# LSF0204RGYR.net
KiCad netlist of a schematic drawn in EAGLE
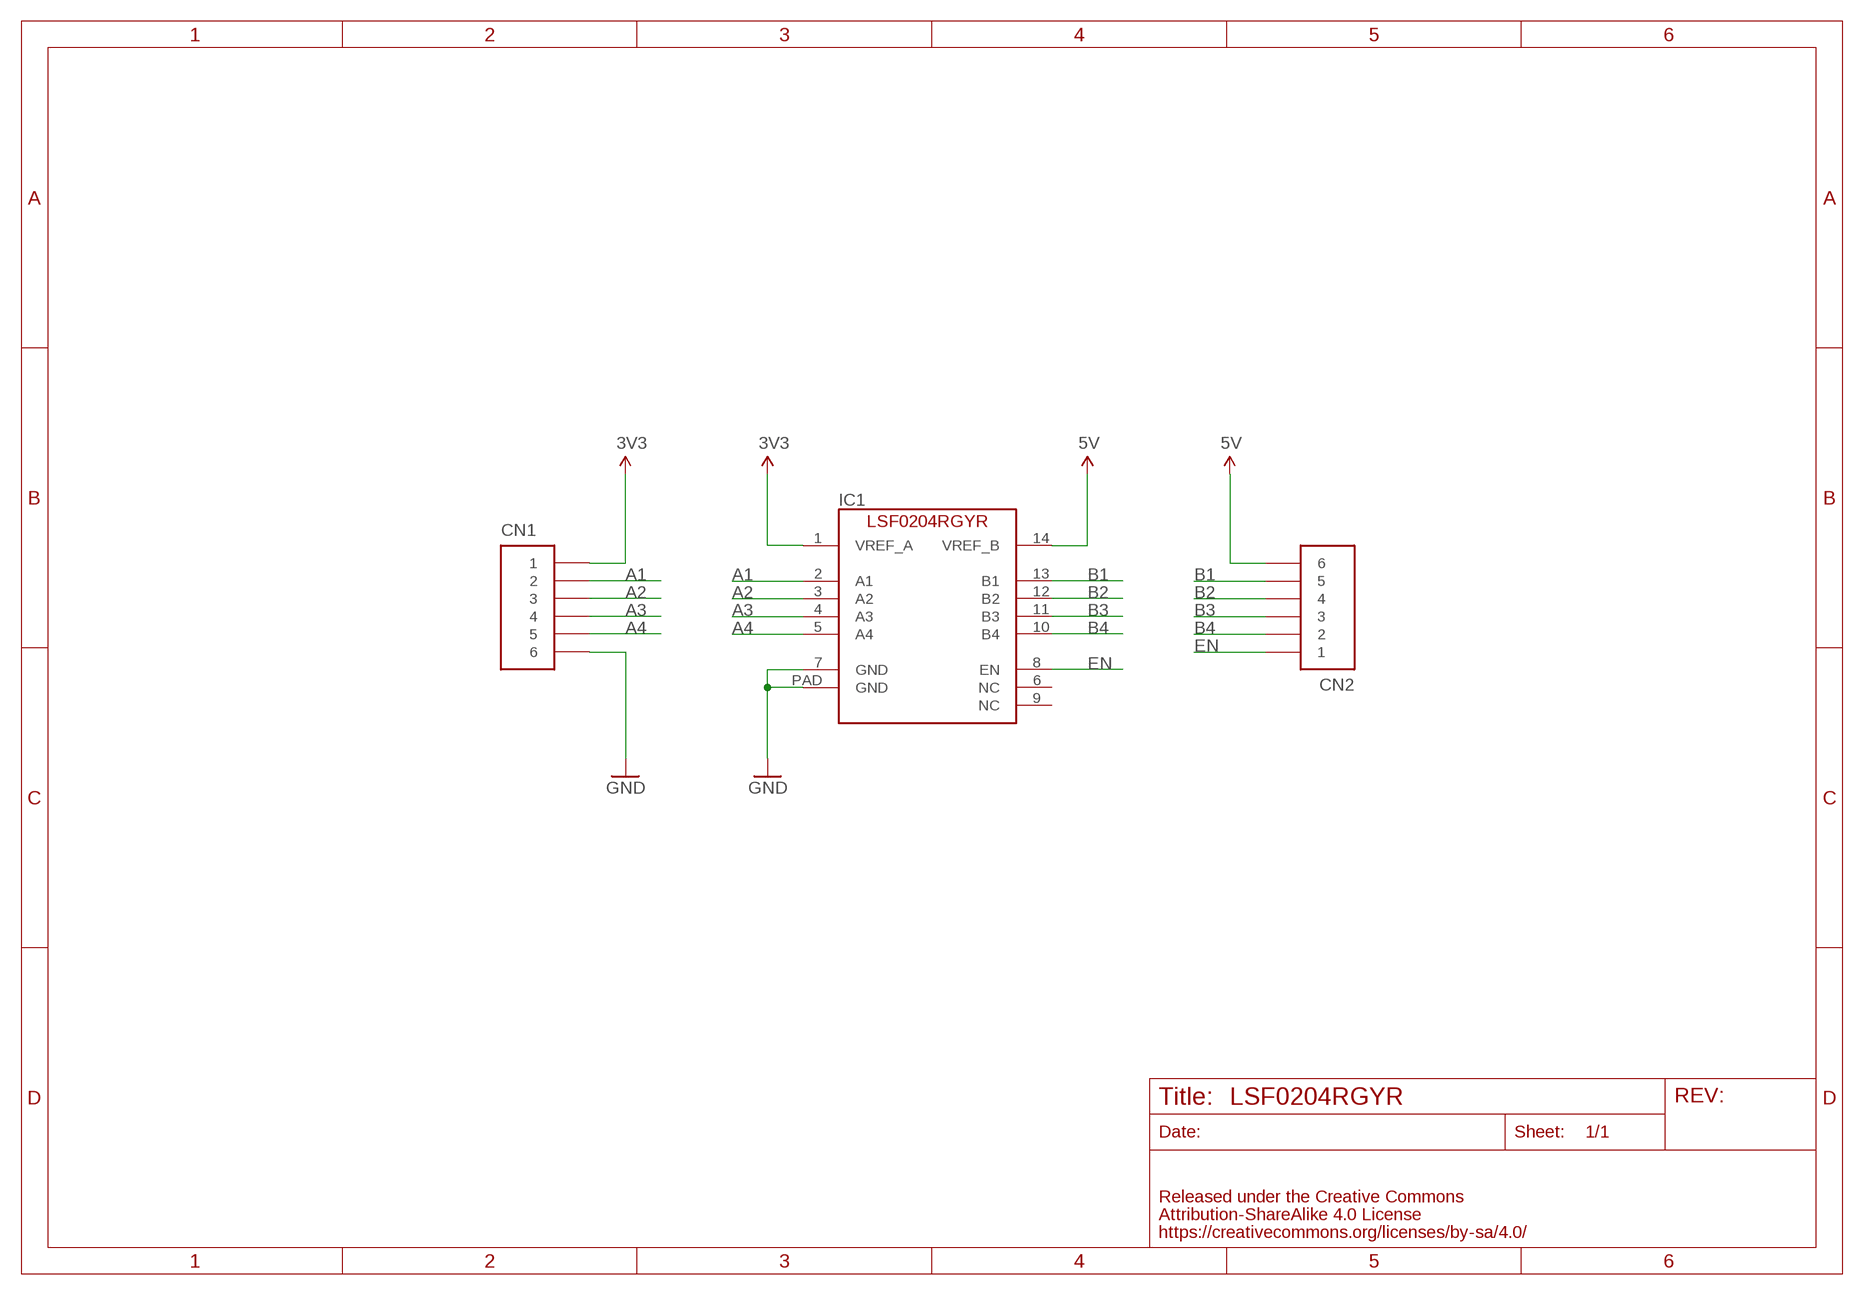
[diagram p0: schematic, sheet 1]

(export (version "E")
  (design (tool "Eeschema 10.0.6"))
  (components
    (comp (ref "CN1")
      (value "PIN_HEADER_1X6-SNEAKY")
      (footprint "eagle-import:PIN_1X6_SNEAKY")
      (libsource (lib "eagle-import") (part "PIN_HEADER_1X6-SNEAKY"))
    )
    (comp (ref "CN2")
      (value "PIN_HEADER_1X6-SNEAKY")
      (footprint "eagle-import:PIN_1X6_SNEAKY")
      (libsource (lib "eagle-import") (part "PIN_HEADER_1X6-SNEAKY"))
    )
    (comp (ref "IC1")
      (value "LSF0204RGYR")
      (footprint "eagle-import:VQFN-14")
      (libsource (lib "eagle-import") (part "LSF0204RGYR"))
    )
  )
  (nets
    (net (code "1") (name "/A1") (class "Default")
      (node (ref "CN1") (pin "2") (pinfunction "2_2") (pintype "bidirectional"))
      (node (ref "IC1") (pin "2") (pinfunction "A1_2") (pintype "bidirectional"))
    )
    (net (code "2") (name "/A2") (class "Default")
      (node (ref "CN1") (pin "3") (pinfunction "3_3") (pintype "bidirectional"))
      (node (ref "IC1") (pin "3") (pinfunction "A2_3") (pintype "bidirectional"))
    )
    (net (code "3") (name "/A3") (class "Default")
      (node (ref "CN1") (pin "4") (pinfunction "4_4") (pintype "bidirectional"))
      (node (ref "IC1") (pin "4") (pinfunction "A3_4") (pintype "bidirectional"))
    )
    (net (code "4") (name "/A4") (class "Default")
      (node (ref "CN1") (pin "5") (pinfunction "5_5") (pintype "bidirectional"))
      (node (ref "IC1") (pin "5") (pinfunction "A4_5") (pintype "bidirectional"))
    )
    (net (code "5") (name "/B1") (class "Default")
      (node (ref "CN2") (pin "5") (pinfunction "5_5") (pintype "bidirectional"))
      (node (ref "IC1") (pin "13") (pinfunction "B1_13") (pintype "bidirectional"))
    )
    (net (code "6") (name "/B2") (class "Default")
      (node (ref "CN2") (pin "4") (pinfunction "4_4") (pintype "bidirectional"))
      (node (ref "IC1") (pin "12") (pinfunction "B2_12") (pintype "bidirectional"))
    )
    (net (code "7") (name "/B3") (class "Default")
      (node (ref "CN2") (pin "3") (pinfunction "3_3") (pintype "bidirectional"))
      (node (ref "IC1") (pin "11") (pinfunction "B3_11") (pintype "bidirectional"))
    )
    (net (code "8") (name "/B4") (class "Default")
      (node (ref "CN2") (pin "2") (pinfunction "2_2") (pintype "bidirectional"))
      (node (ref "IC1") (pin "10") (pinfunction "B4_10") (pintype "bidirectional"))
    )
    (net (code "9") (name "/EN") (class "Default")
      (node (ref "CN2") (pin "1") (pinfunction "1_1") (pintype "bidirectional"))
      (node (ref "IC1") (pin "8") (pinfunction "EN_8") (pintype "bidirectional"))
    )
    (net (code "10") (name "3V3") (class "Default")
      (node (ref "CN1") (pin "1") (pinfunction "1_1") (pintype "bidirectional"))
      (node (ref "IC1") (pin "1") (pinfunction "VREF_A_1") (pintype "bidirectional"))
    )
    (net (code "11") (name "5V") (class "Default")
      (node (ref "CN2") (pin "6") (pinfunction "6_6") (pintype "bidirectional"))
      (node (ref "IC1") (pin "14") (pinfunction "VREF_B_14") (pintype "bidirectional"))
    )
    (net (code "12") (name "GND") (class "Default")
      (node (ref "CN1") (pin "6") (pinfunction "6_6") (pintype "bidirectional"))
      (node (ref "IC1") (pin "7") (pinfunction "GND_7") (pintype "bidirectional"))
      (node (ref "IC1") (pin "PAD") (pinfunction "GND_PAD") (pintype "bidirectional"))
    )
    (net (code "13") (name "unconnected-(IC1-NC-Pad6)") (class "Default")
      (node (ref "IC1") (pin "6") (pinfunction "NC_6") (pintype "bidirectional"))
    )
    (net (code "14") (name "unconnected-(IC1-NC-Pad9)") (class "Default")
      (node (ref "IC1") (pin "9") (pinfunction "NC_9") (pintype "bidirectional"))
    )
  )
)
